# L293D_Driver.net
KiCad netlist of a schematic drawn in EAGLE
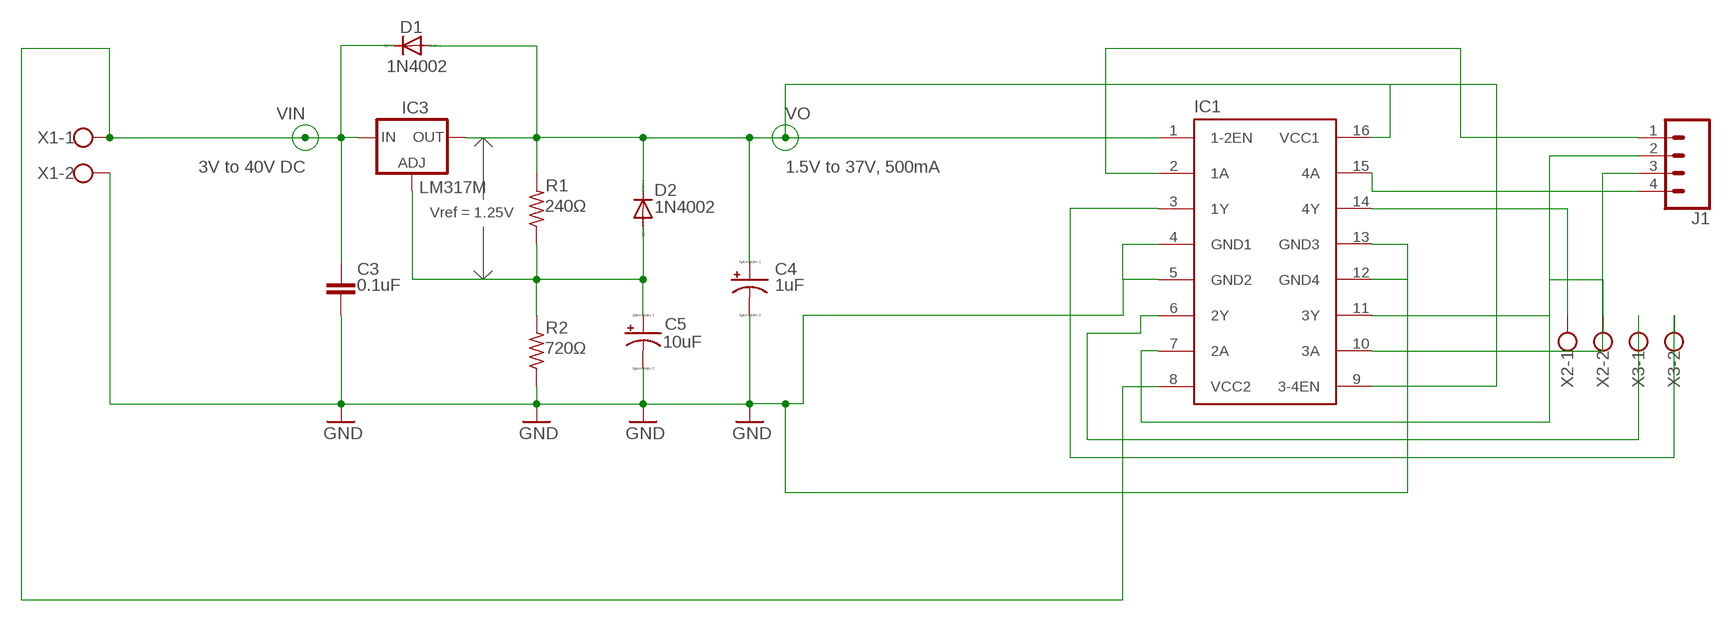
[diagram p0: schematic, sheet 1]

(export (version "E")
  (design (tool "Eeschema 10.0.6"))
  (components
    (comp (ref "C3")
      (value "0.1uF")
      (footprint "eagle-import:C075-052X106")
      (libsource (lib "eagle-import") (part "C-EU075-052X106"))
    )
    (comp (ref "C4")
      (value "1uF")
      (footprint "eagle-import:085CS_1AR")
      (libsource (lib "eagle-import") (part "CPOL-US085CS-1AR"))
    )
    (comp (ref "C5")
      (value "10uF")
      (footprint "eagle-import:085CS_1AR")
      (libsource (lib "eagle-import") (part "CPOL-US085CS-1AR"))
    )
    (comp (ref "D1")
      (value "1N4002")
      (footprint "eagle-import:DO41-10")
      (libsource (lib "eagle-import") (part "1N4004"))
    )
    (comp (ref "D2")
      (value "1N4002")
      (footprint "eagle-import:DO41-10")
      (libsource (lib "eagle-import") (part "1N4004"))
    )
    (comp (ref "IC1")
      (value "L293D")
      (footprint "eagle-import:DIL16")
      (libsource (lib "eagle-import") (part "L293D"))
    )
    (comp (ref "IC3")
      (value "LM317MBSTT3")
      (footprint "eagle-import:SOT223")
      (fields (field (name "PARTNUMBER") "LM317M"))
      (libsource (lib "eagle-import") (part "LM317?MBSTT3"))
    )
    (comp (ref "J1")
      (value "CONN_04PTH")
      (footprint "eagle-import:1X04")
      (libsource (lib "eagle-import") (part "CONN_04PTH"))
    )
    (comp (ref "R1")
      (value "240Ω")
      (footprint "eagle-import:M0805")
      (libsource (lib "eagle-import") (part "R-US_M0805"))
    )
    (comp (ref "R2")
      (value "720Ω")
      (footprint "eagle-import:M0805")
      (libsource (lib "eagle-import") (part "R-US_M0805"))
    )
    (comp (ref "X1")
      (value "W237-102")
      (footprint "eagle-import:W237-102")
      (fields (field (name "MPN") "237-102"))
      (libsource (lib "eagle-import") (part "W237-102"))
    )
    (comp (ref "X2")
      (value "W237-102")
      (footprint "eagle-import:W237-102")
      (fields (field (name "MPN") "237-102"))
      (libsource (lib "eagle-import") (part "W237-102"))
    )
    (comp (ref "X3")
      (value "W237-102")
      (footprint "eagle-import:W237-102")
      (fields (field (name "MPN") "237-102"))
      (libsource (lib "eagle-import") (part "W237-102"))
    )
  )
  (nets
    (net (code "1") (name "/VIN") (class "Default")
      (node (ref "C3") (pin "1") (pinfunction "1_1") (pintype "passive"))
      (node (ref "D1") (pin "C") (pinfunction "C_C") (pintype "passive"))
      (node (ref "IC1") (pin "8") (pinfunction "VCC2_8") (pintype "power_in"))
      (node (ref "IC3") (pin "3") (pinfunction "IN_3") (pintype "input"))
      (node (ref "X1") (pin "1") (pinfunction "KL_1") (pintype "passive"))
    )
    (net (code "2") (name "/VO") (class "Default")
      (node (ref "C4") (pin "+") (pinfunction "+_+") (pintype "passive"))
      (node (ref "D1") (pin "A") (pinfunction "A_A") (pintype "passive"))
      (node (ref "D2") (pin "C") (pinfunction "C_C") (pintype "passive"))
      (node (ref "IC1") (pin "1") (pinfunction "1-2EN_1") (pintype "input"))
      (node (ref "IC1") (pin "16") (pinfunction "VCC1_16") (pintype "power_in"))
      (node (ref "IC1") (pin "9") (pinfunction "3-4EN_9") (pintype "input"))
      (node (ref "IC3") (pin "4") (pinfunction "OUT_4") (pintype "passive"))
      (node (ref "R1") (pin "2") (pinfunction "2_2") (pintype "passive"))
    )
    (net (code "3") (name "GND") (class "Default")
      (node (ref "C3") (pin "2") (pinfunction "2_2") (pintype "passive"))
      (node (ref "C4") (pin "-") (pinfunction "-_-") (pintype "passive"))
      (node (ref "C5") (pin "-") (pinfunction "-_-") (pintype "passive"))
      (node (ref "IC1") (pin "12") (pinfunction "GND4_12") (pintype "power_in"))
      (node (ref "IC1") (pin "13") (pinfunction "GND3_13") (pintype "power_in"))
      (node (ref "IC1") (pin "4") (pinfunction "GND1_4") (pintype "power_in"))
      (node (ref "IC1") (pin "5") (pinfunction "GND2_5") (pintype "power_in"))
      (node (ref "R2") (pin "1") (pinfunction "1_1") (pintype "passive"))
      (node (ref "X1") (pin "2") (pinfunction "KL_2") (pintype "passive"))
    )
    (net (code "4") (name "Net-(IC1-1A)") (class "Default")
      (node (ref "IC1") (pin "2") (pinfunction "1A_2") (pintype "input"))
      (node (ref "J1") (pin "1") (pinfunction "1_1") (pintype "passive"))
    )
    (net (code "5") (name "Net-(IC1-1Y)") (class "Default")
      (node (ref "IC1") (pin "3") (pinfunction "1Y_3") (pintype "output"))
      (node (ref "X3") (pin "2") (pinfunction "KL_2") (pintype "passive"))
    )
    (net (code "6") (name "Net-(IC1-2A)") (class "Default")
      (node (ref "IC1") (pin "7") (pinfunction "2A_7") (pintype "input"))
      (node (ref "J1") (pin "2") (pinfunction "2_2") (pintype "passive"))
    )
    (net (code "7") (name "Net-(IC1-2Y)") (class "Default")
      (node (ref "IC1") (pin "6") (pinfunction "2Y_6") (pintype "output"))
      (node (ref "X3") (pin "1") (pinfunction "KL_1") (pintype "passive"))
    )
    (net (code "8") (name "Net-(IC1-3A)") (class "Default")
      (node (ref "IC1") (pin "10") (pinfunction "3A_10") (pintype "input"))
      (node (ref "J1") (pin "3") (pinfunction "3_3") (pintype "passive"))
    )
    (net (code "9") (name "Net-(IC1-3Y)") (class "Default")
      (node (ref "IC1") (pin "11") (pinfunction "3Y_11") (pintype "output"))
      (node (ref "X2") (pin "2") (pinfunction "KL_2") (pintype "passive"))
    )
    (net (code "10") (name "Net-(IC1-4A)") (class "Default")
      (node (ref "IC1") (pin "15") (pinfunction "4A_15") (pintype "input"))
      (node (ref "J1") (pin "4") (pinfunction "4_4") (pintype "passive"))
    )
    (net (code "11") (name "Net-(IC1-4Y)") (class "Default")
      (node (ref "IC1") (pin "14") (pinfunction "4Y_14") (pintype "output"))
      (node (ref "X2") (pin "1") (pinfunction "KL_1") (pintype "passive"))
    )
    (net (code "12") (name "Net-(IC3-ADJ)") (class "Default")
      (node (ref "C5") (pin "+") (pinfunction "+_+") (pintype "passive"))
      (node (ref "D2") (pin "A") (pinfunction "A_A") (pintype "passive"))
      (node (ref "IC3") (pin "1") (pinfunction "ADJ_1") (pintype "input"))
      (node (ref "R1") (pin "1") (pinfunction "1_1") (pintype "passive"))
      (node (ref "R2") (pin "2") (pinfunction "2_2") (pintype "passive"))
    )
  )
)
